# Energetski_deo.net
KiCad netlist of a schematic drawn in Altium Designer
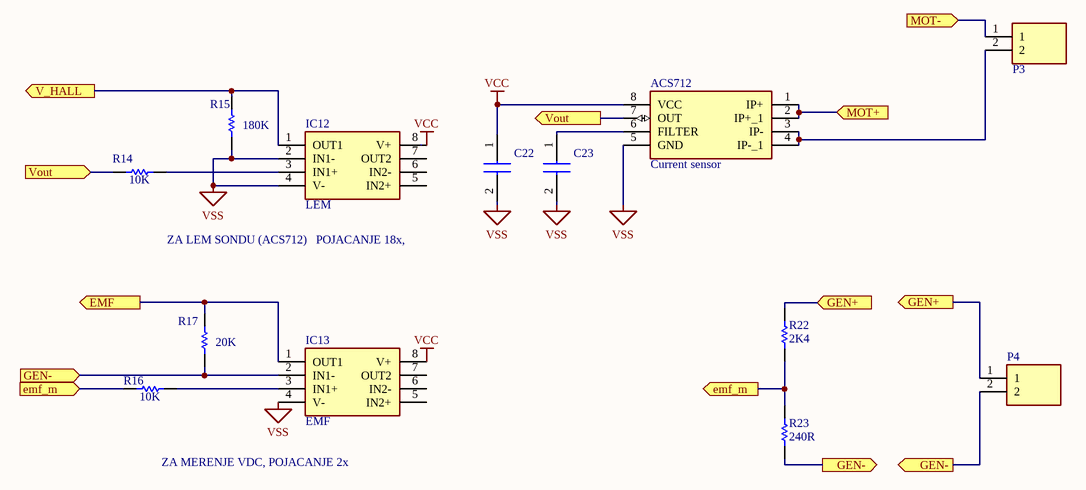
[diagram p0: Energetski deo.SchDoc]

(export (version "E")
  (design (tool "Eeschema 10.0.6"))
  (components
    (comp (ref "ACS712")
      (value "Current sensor")
      (footprint "SamacSys:SOIC127P600X175-8N")
      (description "ACS712ELCTR-05B-T")
      (fields (field (name "RS PART NUMBER") "6807131P"))
      (libsource (lib "Coper") (part "Current sensor"))
    )
    (comp (ref "C22")
      (value "C0805C104K9RACTU")
      (footprint "CAP10, 0.1uF, 6.4V")
      (description "CER 0.1uF, 6.3V")
      (fields (field (name "MOUSER PART NUMBER") "80-C0805C104K9R"))
      (libsource (lib "Coper") (part "Cap10"))
    )
    (comp (ref "C23")
      (value "C1206Y102K9RAC7800")
      (footprint "CAP9, 1000pF, 6.3V")
      (description "CER 1000pF, 6.3V")
      (fields
        (field (name "MANUFACTURER_PART_NUMBER") "C1206Y102K9RACTU")
        (field (name "MOUSER PART NUMBER") "80-C1206Y102K9R")
      )
      (libsource (lib "Coper") (part "Cap9"))
    )
    (comp (ref "IC12")
      (value "LEM")
      (footprint "SamacSys:SOIC127P600X175-8N")
      (description "LM358BAIDR, OP AMP")
      (fields
        (field (name "MANUFACTURER_PART_NUMBER") "LM358BAIDR")
        (field (name "MOUSER PART NUMBER") "595-LM358BAIDR")
      )
      (libsource (lib "Coper") (part "IC5"))
    )
    (comp (ref "IC13")
      (value "EMF")
      (footprint "SamacSys:SOIC127P600X175-8N")
      (description "LM358BAIDR, OP AMP")
      (fields
        (field (name "MANUFACTURER_PART_NUMBER") "LM358BAIDR")
        (field (name "MOUSER PART NUMBER") "595-LM358BAIDR")
      )
      (libsource (lib "Coper") (part "IC5"))
    )
    (comp (ref "P3")
      (value "Connector 2")
      (footprint "Coper:HEADER 2 PIN")
      (description "Connector, 2 pin")
      (fields
        (field (name "DIGI-KEY PART NUMBER") "A98076-ND")
        (field (name "MANUFACTURER") "TE Connectivity AMP Connectors")
      )
      (libsource (lib "Coper") (part "Connector 2"))
    )
    (comp (ref "P4")
      (value "Connector 2")
      (footprint "HEADER 2 PIN")
      (description "Connector, 2 pin")
      (fields
        (field (name "DIGI-KEY PART NUMBER") "A98076-ND")
        (field (name "MANUFACTURER") "TE Connectivity AMP Connectors")
      )
      (libsource (lib "Coper") (part "Connector 2"))
    )
    (comp (ref "R14")
      (value "CFR-25JR-52-10K")
      (footprint "RES4, 10K, 0.25W")
      (description "10K, 0,25W")
      (fields (field (name "MOUSER PART NUMBER") "603-CFR-25JR-5210K"))
      (libsource (lib "Coper") (part "Res4"))
    )
    (comp (ref "R15")
      (value "CFR-25JB-52-180K")
      (footprint "RES9, 180K, 0.25W")
      (description "180K, 025W")
      (fields (field (name "DIGI-KEY PART NUMBER") "180KQBK-ND"))
      (libsource (lib "Coper") (part "Res9"))
    )
    (comp (ref "R16")
      (value "CFR-25JR-52-10K")
      (footprint "RES4, 10K, 0.25W")
      (description "10K, 0,25W")
      (fields (field (name "MOUSER PART NUMBER") "603-CFR-25JR-5210K"))
      (libsource (lib "Coper") (part "Res4"))
    )
    (comp (ref "R17")
      (value "CFR-50JB-52-20K")
      (footprint "RES8, 20K, 0.25W")
      (description "20KOhm, 0.5W")
      (fields (field (name "MOUSER PART NUMBER") "603-CFR-50JB-52-20K"))
      (libsource (lib "Coper") (part "Res8"))
    )
    (comp (ref "R22")
      (value "2K4")
      (footprint "RES2, 2K4, 0.25W")
      (description "2K4, 0.25W")
      (fields (field (name "Comment") "270QBK-ND"))
      (libsource (lib "Coper") (part "Res2"))
    )
    (comp (ref "R23")
      (value "240R")
      (footprint "RES1, 240R, 0.25W")
      (description "240 Ohm, 0.25W")
      (fields (field (name "DIGI-KEY PART NUMBER") "270QBK-ND") (field (name "MANUFACTURER") "Yageo"))
      (libsource (lib "Coper") (part "Res1"))
    )
  )
  (nets
    (net (code "1") (name "/EMF") (class "Default")
      (node (ref "IC13") (pin "1") (pinfunction "OUT1_1") (pintype "passive"))
      (node (ref "R17") (pin "2") (pinfunction "2_2") (pintype "passive"))
    )
    (net (code "2") (name "/GEN+") (class "Default")
      (node (ref "P4") (pin "1") (pinfunction "1_1") (pintype "passive"))
      (node (ref "R22") (pin "2") (pinfunction "2_2") (pintype "passive"))
    )
    (net (code "3") (name "/GEN-") (class "Default")
      (node (ref "IC13") (pin "2") (pinfunction "IN1-_2") (pintype "passive"))
      (node (ref "P4") (pin "2") (pinfunction "2_2") (pintype "passive"))
      (node (ref "R17") (pin "1") (pinfunction "1_1") (pintype "passive"))
      (node (ref "R23") (pin "1") (pinfunction "1_1") (pintype "passive"))
    )
    (net (code "4") (name "/MOT+") (class "Default")
      (node (ref "ACS712") (pin "1") (pinfunction "IP+_1") (pintype "passive"))
      (node (ref "ACS712") (pin "2") (pinfunction "IP+_1_2") (pintype "passive"))
    )
    (net (code "5") (name "/MOT-") (class "Default")
      (node (ref "P3") (pin "1") (pinfunction "1_1") (pintype "passive"))
    )
    (net (code "6") (name "/V_HALL") (class "Default")
      (node (ref "IC12") (pin "1") (pinfunction "OUT1_1") (pintype "passive"))
      (node (ref "R15") (pin "2") (pinfunction "2_2") (pintype "passive"))
    )
    (net (code "7") (name "/Vout") (class "Default")
      (node (ref "ACS712") (pin "7") (pinfunction "OUT_7") (pintype "bidirectional"))
      (node (ref "R14") (pin "2") (pinfunction "2_2") (pintype "passive"))
    )
    (net (code "8") (name "/emf_m") (class "Default")
      (node (ref "R16") (pin "2") (pinfunction "2_2") (pintype "passive"))
      (node (ref "R22") (pin "1") (pinfunction "1_1") (pintype "passive"))
      (node (ref "R23") (pin "2") (pinfunction "2_2") (pintype "passive"))
    )
    (net (code "9") (name "Net-(ACS712-FILTER)") (class "Default")
      (node (ref "ACS712") (pin "6") (pinfunction "FILTER_6") (pintype "passive"))
      (node (ref "C23") (pin "1") (pinfunction "1_1") (pintype "passive"))
    )
    (net (code "10") (name "Net-(ACS712-IP-)") (class "Default")
      (node (ref "ACS712") (pin "3") (pinfunction "IP-_3") (pintype "passive"))
      (node (ref "ACS712") (pin "4") (pinfunction "IP-_1_4") (pintype "passive"))
      (node (ref "P3") (pin "2") (pinfunction "2_2") (pintype "passive"))
    )
    (net (code "11") (name "Net-(IC12-IN1+)") (class "Default")
      (node (ref "IC12") (pin "3") (pinfunction "IN1+_3") (pintype "passive"))
      (node (ref "R14") (pin "1") (pinfunction "1_1") (pintype "passive"))
    )
    (net (code "12") (name "Net-(IC13-IN1+)") (class "Default")
      (node (ref "IC13") (pin "3") (pinfunction "IN1+_3") (pintype "passive"))
      (node (ref "R16") (pin "1") (pinfunction "1_1") (pintype "passive"))
    )
    (net (code "13") (name "VCC") (class "Default")
      (node (ref "ACS712") (pin "8") (pinfunction "VCC_8") (pintype "power_in"))
      (node (ref "C22") (pin "1") (pinfunction "1_1") (pintype "passive"))
      (node (ref "IC12") (pin "8") (pinfunction "V+_8") (pintype "passive"))
      (node (ref "IC13") (pin "8") (pinfunction "V+_8") (pintype "passive"))
    )
    (net (code "14") (name "VSS") (class "Default")
      (node (ref "ACS712") (pin "5") (pinfunction "GND_5") (pintype "power_in"))
      (node (ref "C22") (pin "2") (pinfunction "2_2") (pintype "passive"))
      (node (ref "C23") (pin "2") (pinfunction "2_2") (pintype "passive"))
      (node (ref "IC12") (pin "2") (pinfunction "IN1-_2") (pintype "passive"))
      (node (ref "IC12") (pin "4") (pinfunction "V-_4") (pintype "passive"))
      (node (ref "IC13") (pin "4") (pinfunction "V-_4") (pintype "passive"))
      (node (ref "R15") (pin "1") (pinfunction "1_1") (pintype "passive"))
    )
    (net (code "15") (name "unconnected-(IC12-IN2+-Pad5)") (class "Default")
      (node (ref "IC12") (pin "5") (pinfunction "IN2+_5") (pintype "passive"))
    )
    (net (code "16") (name "unconnected-(IC12-IN2--Pad6)") (class "Default")
      (node (ref "IC12") (pin "6") (pinfunction "IN2-_6") (pintype "passive"))
    )
    (net (code "17") (name "unconnected-(IC12-OUT2-Pad7)") (class "Default")
      (node (ref "IC12") (pin "7") (pinfunction "OUT2_7") (pintype "passive"))
    )
    (net (code "18") (name "unconnected-(IC13-IN2+-Pad5)") (class "Default")
      (node (ref "IC13") (pin "5") (pinfunction "IN2+_5") (pintype "passive"))
    )
    (net (code "19") (name "unconnected-(IC13-IN2--Pad6)") (class "Default")
      (node (ref "IC13") (pin "6") (pinfunction "IN2-_6") (pintype "passive"))
    )
    (net (code "20") (name "unconnected-(IC13-OUT2-Pad7)") (class "Default")
      (node (ref "IC13") (pin "7") (pinfunction "OUT2_7") (pintype "passive"))
    )
  )
)
